# MCU_-_Power_and_I_O.net
KiCad netlist of a schematic drawn in Altium Designer
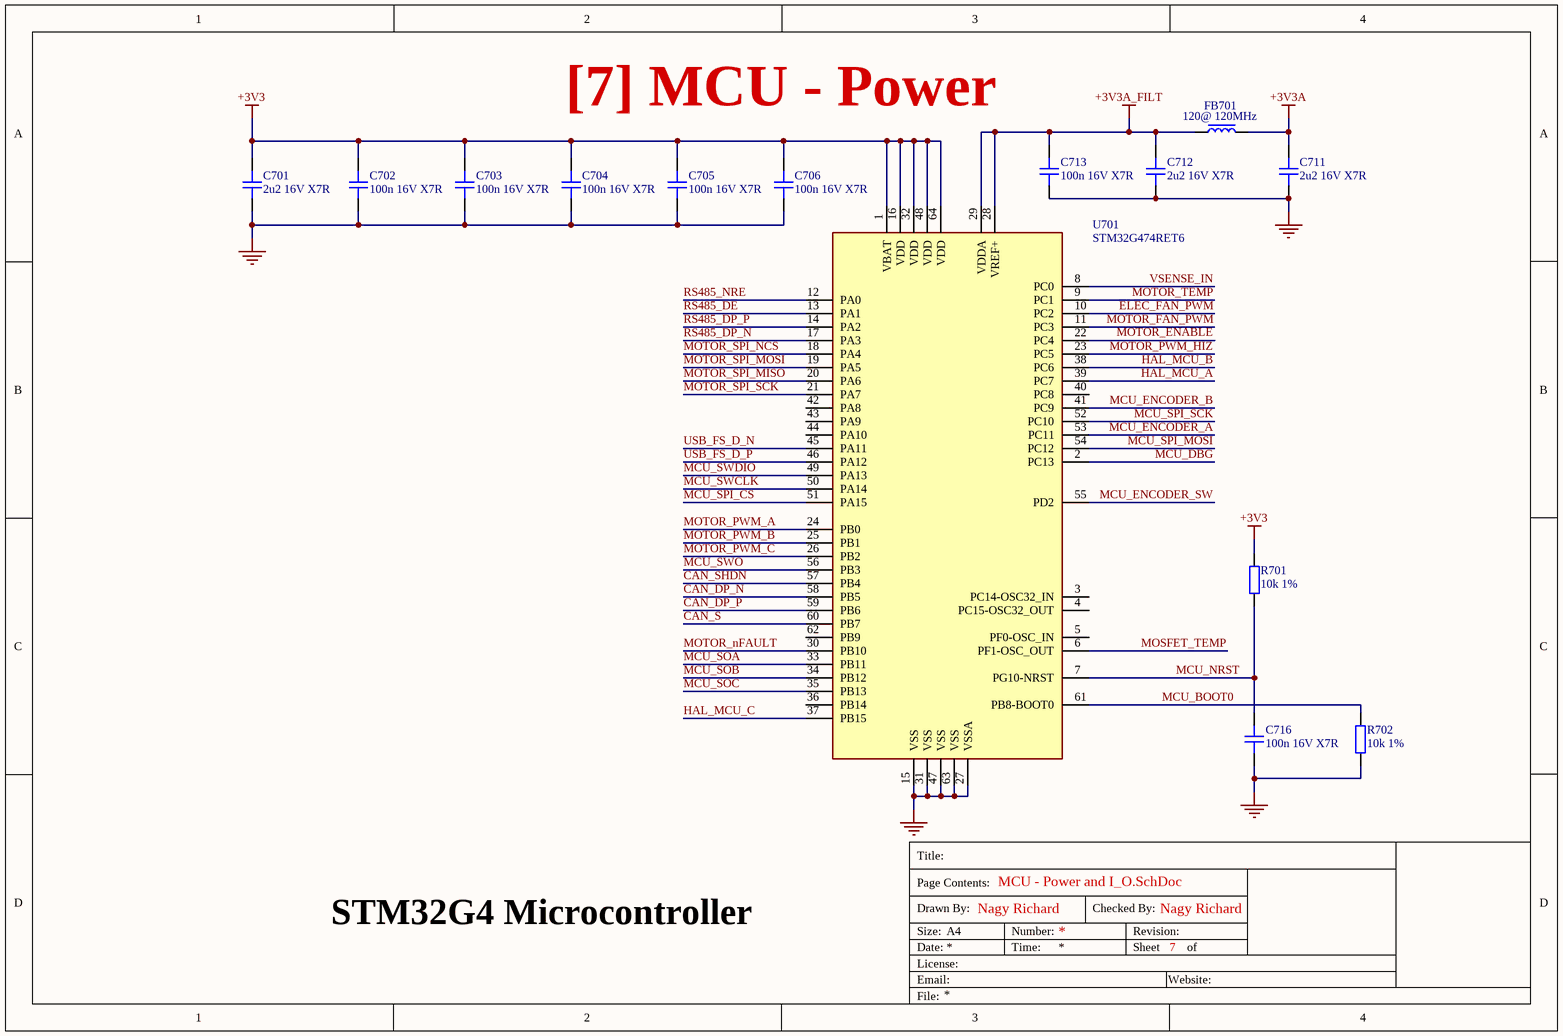
[diagram p0: MCU - Power and I_O.SchDoc]

(export (version "E")
  (design (tool "Eeschema 10.0.6"))
  (components
    (comp (ref "C701")
      (value "2u2 16V X7R")
      (footprint "CAP_0603")
      (description "Capacitor SMD 0603")
      (fields
        (field (name "MANUFACTURER") "YAGEO")
        (field (name "MANUFACTURER PART NUMBER") "CC0603KRX7R7BB225")
      )
      (libsource (lib "Schematic-Lib-PhilsLab") (part "CAP_0603"))
    )
    (comp (ref "C702")
      (value "100n 16V X7R")
      (footprint "CAP_0402")
      (description "Capacitor SMD 0402")
      (fields
        (field (name "MANUFACTURER") "YAGEO")
        (field (name "MANUFACTURER PART NUMBER") "CC0402JRX7R7BB104")
      )
      (libsource (lib "Schematic-Lib-PhilsLab") (part "CAP_0402"))
    )
    (comp (ref "C703")
      (value "100n 16V X7R")
      (footprint "CAP_0402")
      (description "Capacitor SMD 0402")
      (fields
        (field (name "MANUFACTURER") "YAGEO")
        (field (name "MANUFACTURER PART NUMBER") "CC0402JRX7R7BB104")
      )
      (libsource (lib "Schematic-Lib-PhilsLab") (part "CAP_0402"))
    )
    (comp (ref "C704")
      (value "100n 16V X7R")
      (footprint "CAP_0402")
      (description "Capacitor SMD 0402")
      (fields
        (field (name "MANUFACTURER") "YAGEO")
        (field (name "MANUFACTURER PART NUMBER") "CC0402JRX7R7BB104")
      )
      (libsource (lib "Schematic-Lib-PhilsLab") (part "CAP_0402"))
    )
    (comp (ref "C705")
      (value "100n 16V X7R")
      (footprint "CAP_0402")
      (description "Capacitor SMD 0402")
      (fields
        (field (name "MANUFACTURER") "YAGEO")
        (field (name "MANUFACTURER PART NUMBER") "CC0402JRX7R7BB104")
      )
      (libsource (lib "Schematic-Lib-PhilsLab") (part "CAP_0402"))
    )
    (comp (ref "C706")
      (value "100n 16V X7R")
      (footprint "CAP_0402")
      (description "Capacitor SMD 0402")
      (fields
        (field (name "MANUFACTURER") "YAGEO")
        (field (name "MANUFACTURER PART NUMBER") "CC0402JRX7R7BB104")
      )
      (libsource (lib "Schematic-Lib-PhilsLab") (part "CAP_0402"))
    )
    (comp (ref "C711")
      (value "2u2 16V X7R")
      (footprint "CAP_0603")
      (description "Capacitor SMD 0603")
      (fields
        (field (name "MANUFACTURER") "YAGEO")
        (field (name "MANUFACTURER PART NUMBER") "CC0603KRX7R7BB225")
      )
      (libsource (lib "Schematic-Lib-PhilsLab") (part "CAP_0603"))
    )
    (comp (ref "C712")
      (value "2u2 16V X7R")
      (footprint "CAP_0603")
      (description "Capacitor SMD 0603")
      (fields
        (field (name "MANUFACTURER") "YAGEO")
        (field (name "MANUFACTURER PART NUMBER") "CC0603KRX7R7BB225")
      )
      (libsource (lib "Schematic-Lib-PhilsLab") (part "CAP_0603"))
    )
    (comp (ref "C713")
      (value "100n 16V X7R")
      (footprint "CAP_0402")
      (description "Capacitor SMD 0402")
      (fields
        (field (name "MANUFACTURER") "YAGEO")
        (field (name "MANUFACTURER PART NUMBER") "CC0402JRX7R7BB104")
      )
      (libsource (lib "Schematic-Lib-PhilsLab") (part "CAP_0402"))
    )
    (comp (ref "C716")
      (value "100n 16V X7R")
      (footprint "CAP_0402")
      (description "Capacitor SMD 0402")
      (fields
        (field (name "MANUFACTURER") "YAGEO")
        (field (name "MANUFACTURER PART NUMBER") "CC0402JRX7R7BB104")
      )
      (libsource (lib "Schematic-Lib-PhilsLab") (part "CAP_0402"))
    )
    (comp (ref "FB701")
      (value "120@ 120MHz")
      (footprint "FB_0603")
      (description "Ferrite Bead SMD 0603")
      (fields
        (field (name "MANUFACTURER") "TDK")
        (field (name "MANUFACTURER PART NUMBER") "MMZ1608S121ATD25")
      )
      (libsource (lib "Schematic-Lib-PhilsLab") (part "FB_0603"))
    )
    (comp (ref "R701")
      (value "10k 1%")
      (footprint "RES_0402")
      (description "Resistor SMD 0402")
      (fields
        (field (name "MANUFACTURER") "PANASONIC")
        (field (name "MANUFACTURER PART NUMBER") "ERJPA2F1002X")
      )
      (libsource (lib "Schematic-Lib-PhilsLab") (part "RES_0402"))
    )
    (comp (ref "R702")
      (value "10k 1%")
      (footprint "RES_0402")
      (description "Resistor SMD 0402")
      (fields
        (field (name "MANUFACTURER") "PANASONIC")
        (field (name "MANUFACTURER PART NUMBER") "ERJPA2F1002X")
      )
      (libsource (lib "Schematic-Lib-PhilsLab") (part "RES_0402"))
    )
    (comp (ref "U701")
      (value "STM32G474RET6")
      (footprint "QFP50P1200X1200X160-64N")
      (libsource (lib "Schematic-Lib-PhilsLab") (part "STM32G474RET6"))
    )
  )
  (nets
    (net (code "1") (name "+3V3") (class "Default")
      (node (ref "C701") (pin "2") (pinfunction "2_2") (pintype "passive"))
      (node (ref "C702") (pin "2") (pinfunction "2_2") (pintype "passive"))
      (node (ref "C703") (pin "2") (pinfunction "2_2") (pintype "passive"))
      (node (ref "C704") (pin "2") (pinfunction "2_2") (pintype "passive"))
      (node (ref "C705") (pin "2") (pinfunction "2_2") (pintype "passive"))
      (node (ref "C706") (pin "2") (pinfunction "2_2") (pintype "passive"))
      (node (ref "R701") (pin "2") (pinfunction "2_2") (pintype "passive"))
      (node (ref "U701") (pin "1") (pinfunction "VBAT_1") (pintype "passive"))
      (node (ref "U701") (pin "16") (pinfunction "VDD_16") (pintype "passive"))
      (node (ref "U701") (pin "32") (pinfunction "VDD_32") (pintype "passive"))
      (node (ref "U701") (pin "48") (pinfunction "VDD_48") (pintype "passive"))
      (node (ref "U701") (pin "64") (pinfunction "VDD_64") (pintype "passive"))
    )
    (net (code "2") (name "+3V3A") (class "Default")
      (node (ref "C711") (pin "2") (pinfunction "2_2") (pintype "passive"))
      (node (ref "FB701") (pin "2") (pinfunction "2_2") (pintype "passive"))
    )
    (net (code "3") (name "+3V3A_FILT") (class "Default")
      (node (ref "C712") (pin "2") (pinfunction "2_2") (pintype "passive"))
      (node (ref "C713") (pin "2") (pinfunction "2_2") (pintype "passive"))
      (node (ref "FB701") (pin "1") (pinfunction "1_1") (pintype "passive"))
      (node (ref "U701") (pin "28") (pinfunction "VREF+_28") (pintype "passive"))
      (node (ref "U701") (pin "29") (pinfunction "VDDA_29") (pintype "passive"))
    )
    (net (code "4") (name "/CAN_DP_N") (class "Default")
      (node (ref "U701") (pin "58") (pinfunction "PB5_58") (pintype "passive"))
    )
    (net (code "5") (name "/CAN_DP_P") (class "Default")
      (node (ref "U701") (pin "59") (pinfunction "PB6_59") (pintype "passive"))
    )
    (net (code "6") (name "/CAN_S") (class "Default")
      (node (ref "U701") (pin "60") (pinfunction "PB7_60") (pintype "passive"))
    )
    (net (code "7") (name "/CAN_SHDN") (class "Default")
      (node (ref "U701") (pin "57") (pinfunction "PB4_57") (pintype "passive"))
    )
    (net (code "8") (name "/ELEC_FAN_PWM") (class "Default")
      (node (ref "U701") (pin "10") (pinfunction "PC2_10") (pintype "passive"))
    )
    (net (code "9") (name "/HAL_MCU_A") (class "Default")
      (node (ref "U701") (pin "39") (pinfunction "PC7_39") (pintype "passive"))
    )
    (net (code "10") (name "/HAL_MCU_B") (class "Default")
      (node (ref "U701") (pin "38") (pinfunction "PC6_38") (pintype "passive"))
    )
    (net (code "11") (name "/HAL_MCU_C") (class "Default")
      (node (ref "U701") (pin "37") (pinfunction "PB15_37") (pintype "passive"))
    )
    (net (code "12") (name "/MCU_BOOT0") (class "Default")
      (node (ref "R702") (pin "2") (pinfunction "2_2") (pintype "passive"))
      (node (ref "U701") (pin "61") (pinfunction "PB8-BOOT0_61") (pintype "passive"))
    )
    (net (code "13") (name "/MCU_DBG") (class "Default")
      (node (ref "U701") (pin "2") (pinfunction "PC13_2") (pintype "passive"))
    )
    (net (code "14") (name "/MCU_ENCODER_A") (class "Default")
      (node (ref "U701") (pin "53") (pinfunction "PC11_53") (pintype "passive"))
    )
    (net (code "15") (name "/MCU_ENCODER_B") (class "Default")
      (node (ref "U701") (pin "41") (pinfunction "PC9_41") (pintype "passive"))
    )
    (net (code "16") (name "/MCU_ENCODER_SW") (class "Default")
      (node (ref "U701") (pin "55") (pinfunction "PD2_55") (pintype "passive"))
    )
    (net (code "17") (name "/MCU_NRST") (class "Default")
      (node (ref "C716") (pin "2") (pinfunction "2_2") (pintype "passive"))
      (node (ref "R701") (pin "1") (pinfunction "1_1") (pintype "passive"))
      (node (ref "U701") (pin "7") (pinfunction "PG10-NRST_7") (pintype "passive"))
    )
    (net (code "18") (name "/MCU_SOA") (class "Default")
      (node (ref "U701") (pin "33") (pinfunction "PB11_33") (pintype "passive"))
    )
    (net (code "19") (name "/MCU_SOB") (class "Default")
      (node (ref "U701") (pin "34") (pinfunction "PB12_34") (pintype "passive"))
    )
    (net (code "20") (name "/MCU_SOC") (class "Default")
      (node (ref "U701") (pin "35") (pinfunction "PB13_35") (pintype "passive"))
    )
    (net (code "21") (name "/MCU_SPI_CS") (class "Default")
      (node (ref "U701") (pin "51") (pinfunction "PA15_51") (pintype "passive"))
    )
    (net (code "22") (name "/MCU_SPI_MOSI") (class "Default")
      (node (ref "U701") (pin "54") (pinfunction "PC12_54") (pintype "passive"))
    )
    (net (code "23") (name "/MCU_SPI_SCK") (class "Default")
      (node (ref "U701") (pin "52") (pinfunction "PC10_52") (pintype "passive"))
    )
    (net (code "24") (name "/MCU_SWCLK") (class "Default")
      (node (ref "U701") (pin "50") (pinfunction "PA14_50") (pintype "passive"))
    )
    (net (code "25") (name "/MCU_SWDIO") (class "Default")
      (node (ref "U701") (pin "49") (pinfunction "PA13_49") (pintype "passive"))
    )
    (net (code "26") (name "/MCU_SWO") (class "Default")
      (node (ref "U701") (pin "56") (pinfunction "PB3_56") (pintype "passive"))
    )
    (net (code "27") (name "/MOSFET_TEMP") (class "Default")
      (node (ref "U701") (pin "6") (pinfunction "PF1-OSC_OUT_6") (pintype "passive"))
    )
    (net (code "28") (name "/MOTOR_ENABLE") (class "Default")
      (node (ref "U701") (pin "22") (pinfunction "PC4_22") (pintype "passive"))
    )
    (net (code "29") (name "/MOTOR_FAN_PWM") (class "Default")
      (node (ref "U701") (pin "11") (pinfunction "PC3_11") (pintype "passive"))
    )
    (net (code "30") (name "/MOTOR_PWM_A") (class "Default")
      (node (ref "U701") (pin "24") (pinfunction "PB0_24") (pintype "passive"))
    )
    (net (code "31") (name "/MOTOR_PWM_B") (class "Default")
      (node (ref "U701") (pin "25") (pinfunction "PB1_25") (pintype "passive"))
    )
    (net (code "32") (name "/MOTOR_PWM_C") (class "Default")
      (node (ref "U701") (pin "26") (pinfunction "PB2_26") (pintype "passive"))
    )
    (net (code "33") (name "/MOTOR_PWM_HIZ") (class "Default")
      (node (ref "U701") (pin "23") (pinfunction "PC5_23") (pintype "passive"))
    )
    (net (code "34") (name "/MOTOR_SPI_MISO") (class "Default")
      (node (ref "U701") (pin "20") (pinfunction "PA6_20") (pintype "passive"))
    )
    (net (code "35") (name "/MOTOR_SPI_MOSI") (class "Default")
      (node (ref "U701") (pin "19") (pinfunction "PA5_19") (pintype "passive"))
    )
    (net (code "36") (name "/MOTOR_SPI_NCS") (class "Default")
      (node (ref "U701") (pin "18") (pinfunction "PA4_18") (pintype "passive"))
    )
    (net (code "37") (name "/MOTOR_SPI_SCK") (class "Default")
      (node (ref "U701") (pin "21") (pinfunction "PA7_21") (pintype "passive"))
    )
    (net (code "38") (name "/MOTOR_TEMP") (class "Default")
      (node (ref "U701") (pin "9") (pinfunction "PC1_9") (pintype "passive"))
    )
    (net (code "39") (name "/MOTOR_nFAULT") (class "Default")
      (node (ref "U701") (pin "30") (pinfunction "PB10_30") (pintype "passive"))
    )
    (net (code "40") (name "/RS485_DE") (class "Default")
      (node (ref "U701") (pin "13") (pinfunction "PA1_13") (pintype "passive"))
    )
    (net (code "41") (name "/RS485_DP_N") (class "Default")
      (node (ref "U701") (pin "17") (pinfunction "PA3_17") (pintype "passive"))
    )
    (net (code "42") (name "/RS485_DP_P") (class "Default")
      (node (ref "U701") (pin "14") (pinfunction "PA2_14") (pintype "passive"))
    )
    (net (code "43") (name "/RS485_NRE") (class "Default")
      (node (ref "U701") (pin "12") (pinfunction "PA0_12") (pintype "passive"))
    )
    (net (code "44") (name "/USB_FS_D_N") (class "Default")
      (node (ref "U701") (pin "45") (pinfunction "PA11_45") (pintype "passive"))
    )
    (net (code "45") (name "/USB_FS_D_P") (class "Default")
      (node (ref "U701") (pin "46") (pinfunction "PA12_46") (pintype "passive"))
    )
    (net (code "46") (name "/VSENSE_IN") (class "Default")
      (node (ref "U701") (pin "8") (pinfunction "PC0_8") (pintype "passive"))
    )
    (net (code "47") (name "GND") (class "Default")
      (node (ref "C701") (pin "1") (pinfunction "1_1") (pintype "passive"))
      (node (ref "C702") (pin "1") (pinfunction "1_1") (pintype "passive"))
      (node (ref "C703") (pin "1") (pinfunction "1_1") (pintype "passive"))
      (node (ref "C704") (pin "1") (pinfunction "1_1") (pintype "passive"))
      (node (ref "C705") (pin "1") (pinfunction "1_1") (pintype "passive"))
      (node (ref "C706") (pin "1") (pinfunction "1_1") (pintype "passive"))
      (node (ref "C711") (pin "1") (pinfunction "1_1") (pintype "passive"))
      (node (ref "C712") (pin "1") (pinfunction "1_1") (pintype "passive"))
      (node (ref "C713") (pin "1") (pinfunction "1_1") (pintype "passive"))
      (node (ref "C716") (pin "1") (pinfunction "1_1") (pintype "passive"))
      (node (ref "R702") (pin "1") (pinfunction "1_1") (pintype "passive"))
      (node (ref "U701") (pin "15") (pinfunction "VSS_15") (pintype "passive"))
      (node (ref "U701") (pin "27") (pinfunction "VSSA_27") (pintype "passive"))
      (node (ref "U701") (pin "31") (pinfunction "VSS_31") (pintype "passive"))
      (node (ref "U701") (pin "47") (pinfunction "VSS_47") (pintype "passive"))
      (node (ref "U701") (pin "63") (pinfunction "VSS_63") (pintype "passive"))
    )
    (net (code "48") (name "unconnected-(U701-PA8-Pad42)") (class "Default")
      (node (ref "U701") (pin "42") (pinfunction "PA8_42") (pintype "passive"))
    )
    (net (code "49") (name "unconnected-(U701-PA9-Pad43)") (class "Default")
      (node (ref "U701") (pin "43") (pinfunction "PA9_43") (pintype "passive"))
    )
    (net (code "50") (name "unconnected-(U701-PA10-Pad44)") (class "Default")
      (node (ref "U701") (pin "44") (pinfunction "PA10_44") (pintype "passive"))
    )
    (net (code "51") (name "unconnected-(U701-PB9-Pad62)") (class "Default")
      (node (ref "U701") (pin "62") (pinfunction "PB9_62") (pintype "passive"))
    )
    (net (code "52") (name "unconnected-(U701-PB14-Pad36)") (class "Default")
      (node (ref "U701") (pin "36") (pinfunction "PB14_36") (pintype "passive"))
    )
    (net (code "53") (name "unconnected-(U701-PC8-Pad40)") (class "Default")
      (node (ref "U701") (pin "40") (pinfunction "PC8_40") (pintype "passive"))
    )
    (net (code "54") (name "unconnected-(U701-PC14-OSC32_IN-Pad3)") (class "Default")
      (node (ref "U701") (pin "3") (pinfunction "PC14-OSC32_IN_3") (pintype "passive"))
    )
    (net (code "55") (name "unconnected-(U701-PC15-OSC32_OUT-Pad4)") (class "Default")
      (node (ref "U701") (pin "4") (pinfunction "PC15-OSC32_OUT_4") (pintype "passive"))
    )
    (net (code "56") (name "unconnected-(U701-PF0-OSC_IN-Pad5)") (class "Default")
      (node (ref "U701") (pin "5") (pinfunction "PF0-OSC_IN_5") (pintype "passive"))
    )
  )
)
